# node.net
KiCad netlist of a schematic drawn in EAGLE
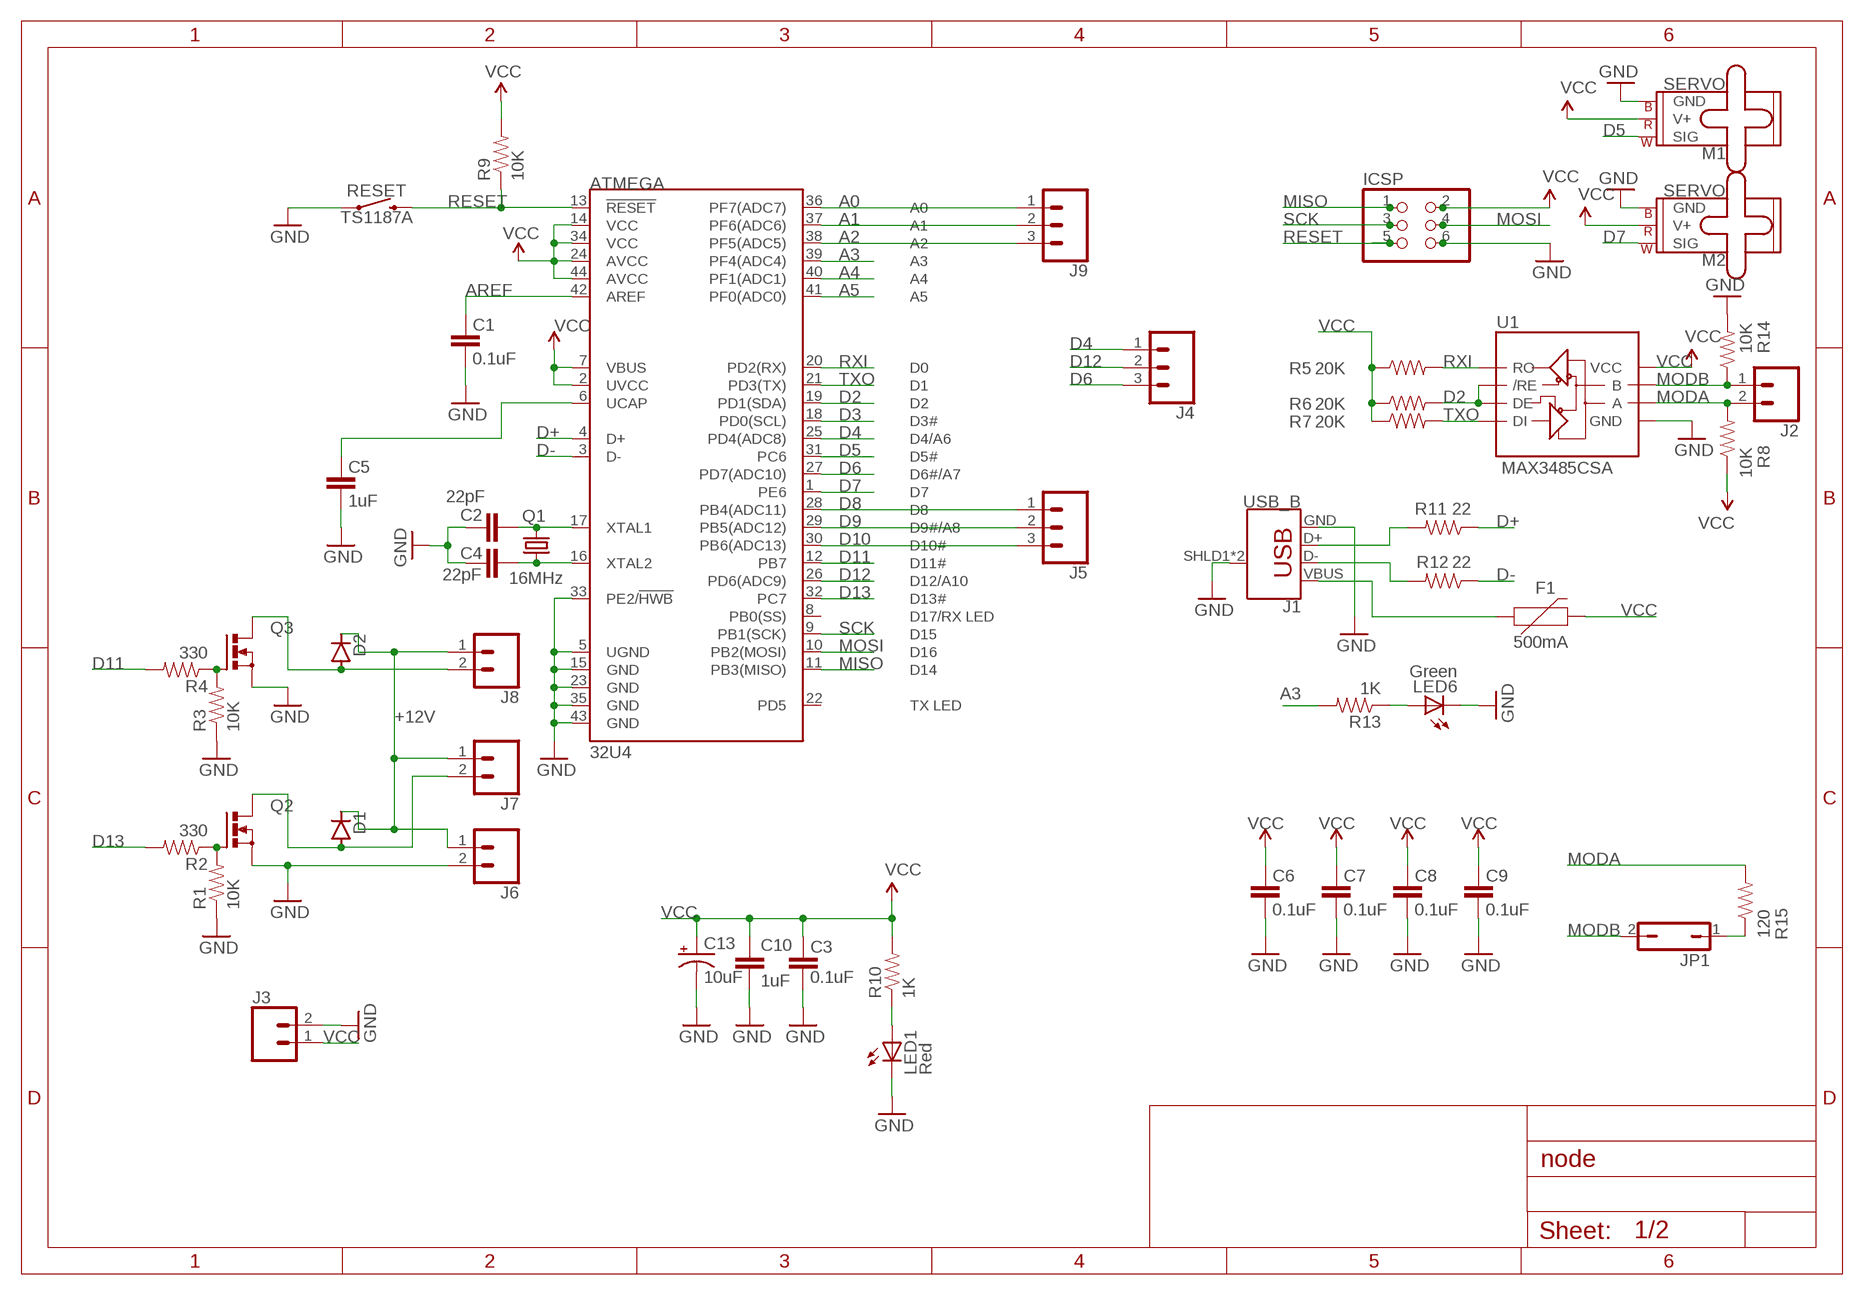
[diagram p0: schematic, sheet 1]
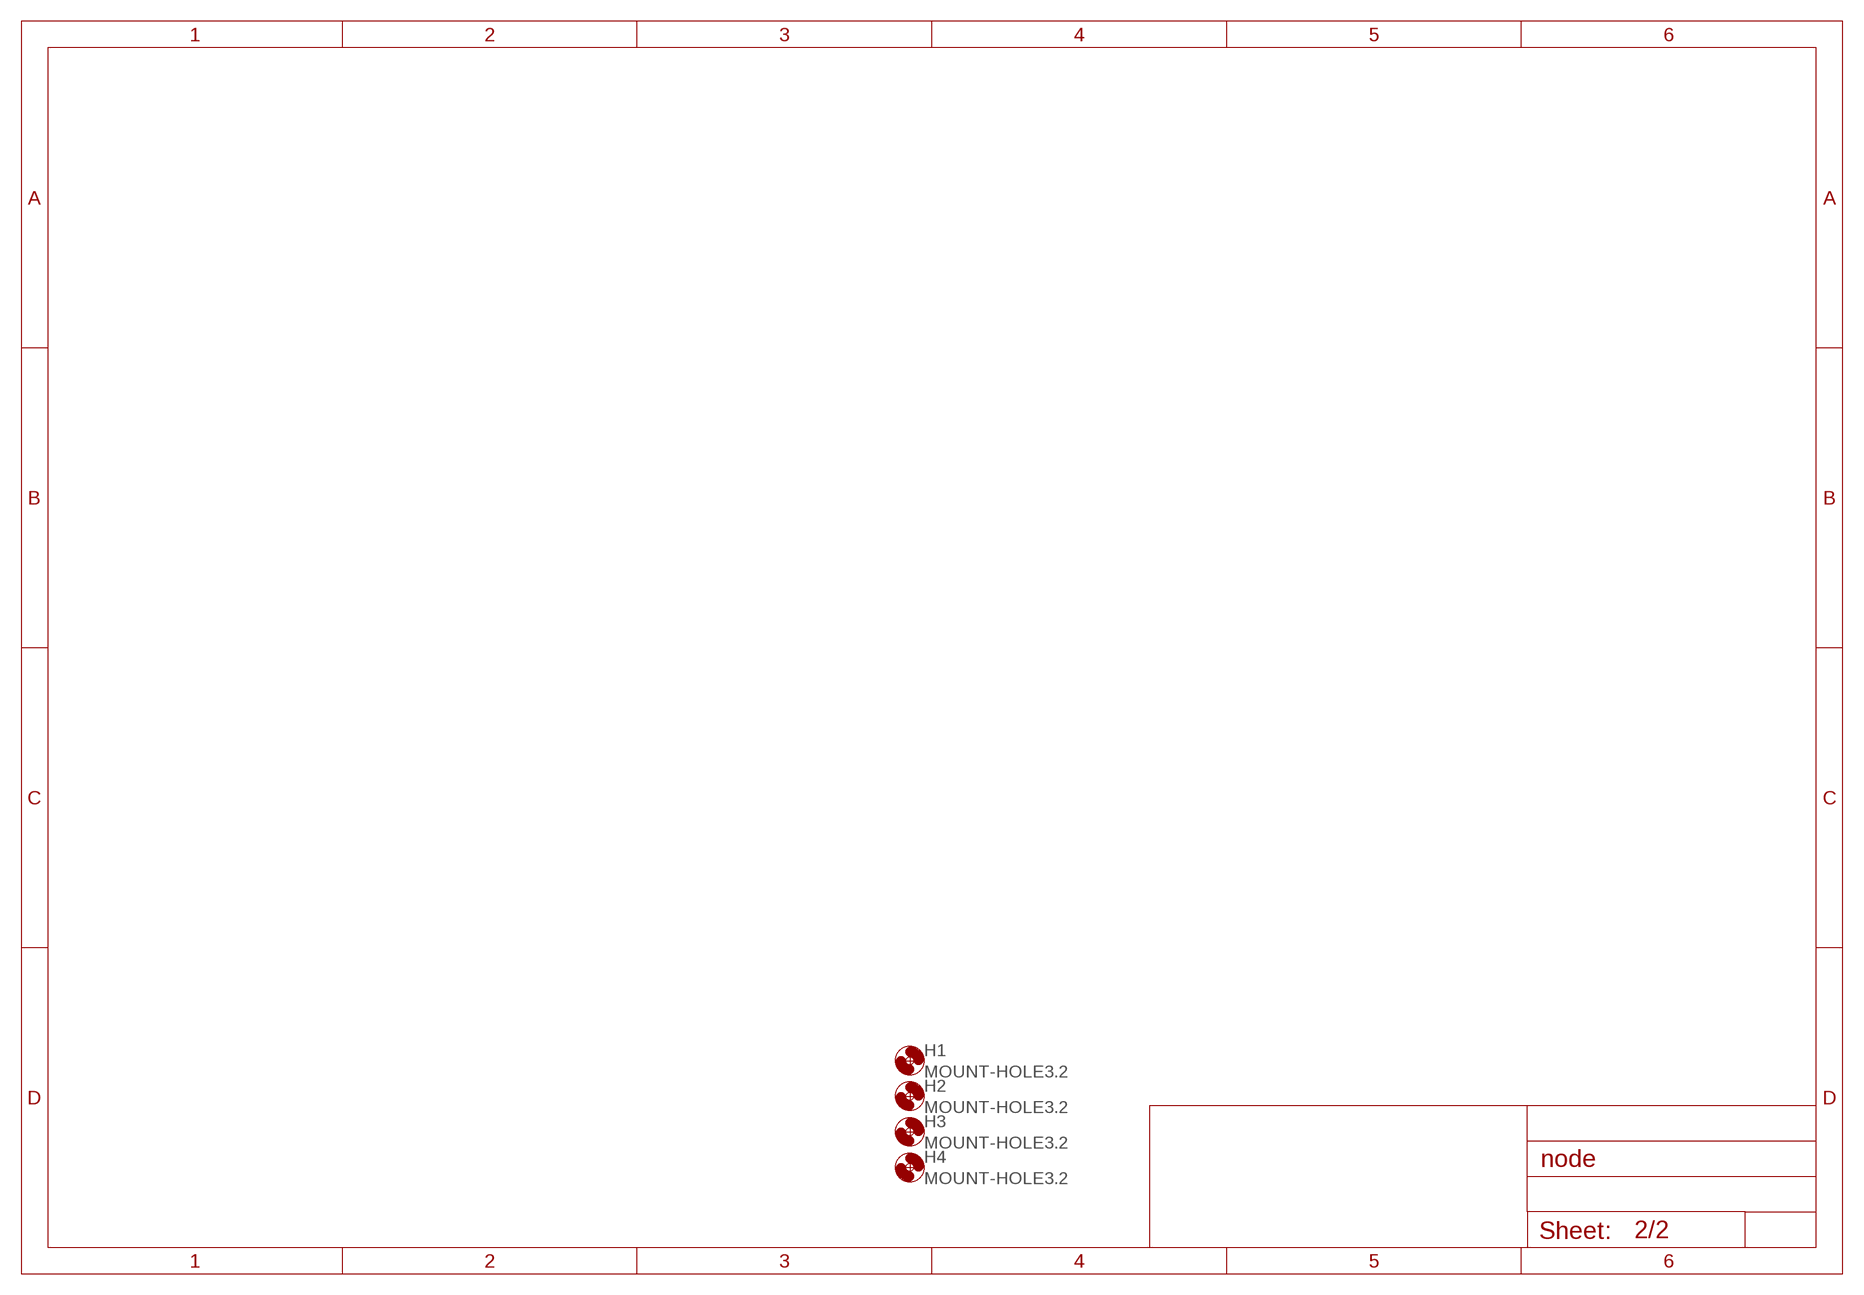
[diagram p1: schematic, sheet 2]

(export (version "E")
  (design (tool "Eeschema 10.0.6"))
  (components
    (comp (ref "H1")
      (value "MOUNT-HOLE3.2")
      (footprint "eagle-import:3,2")
      (libsource (lib "eagle-import") (part "MOUNT-HOLE3.2"))
    )
    (comp (ref "H2")
      (value "MOUNT-HOLE3.2")
      (footprint "eagle-import:3,2")
      (libsource (lib "eagle-import") (part "MOUNT-HOLE3.2"))
    )
    (comp (ref "H3")
      (value "MOUNT-HOLE3.2")
      (footprint "eagle-import:3,2")
      (libsource (lib "eagle-import") (part "MOUNT-HOLE3.2"))
    )
    (comp (ref "H4")
      (value "MOUNT-HOLE3.2")
      (footprint "eagle-import:3,2")
      (libsource (lib "eagle-import") (part "MOUNT-HOLE3.2"))
    )
    (comp (ref "ATMEGA")
      (value "32U4")
      (footprint "eagle-import:QFN-44-NOPAD_1_1")
      (libsource (lib "eagle-import") (part "ATMEGA32U41{colon}1"))
    )
    (comp (ref "C1")
      (value "0.1uF")
      (footprint "eagle-import:0603-CAP")
      (libsource (lib "eagle-import") (part "CAP0603-CAP"))
    )
    (comp (ref "C2")
      (value "22pF")
      (footprint "eagle-import:0603-CAP")
      (libsource (lib "eagle-import") (part "CAP0603-CAP"))
    )
    (comp (ref "C3")
      (value "0.1uF")
      (footprint "eagle-import:0603-CAP")
      (libsource (lib "eagle-import") (part "CAP0603-CAP"))
    )
    (comp (ref "C4")
      (value "22pF")
      (footprint "eagle-import:0603-CAP")
      (libsource (lib "eagle-import") (part "CAP0603-CAP"))
    )
    (comp (ref "C5")
      (value "1uF")
      (footprint "eagle-import:0603-CAP")
      (libsource (lib "eagle-import") (part "CAP0603-CAP"))
    )
    (comp (ref "C6")
      (value "0.1uF")
      (footprint "eagle-import:0603-CAP")
      (libsource (lib "eagle-import") (part "CAP0603-CAP"))
    )
    (comp (ref "C7")
      (value "0.1uF")
      (footprint "eagle-import:0603-CAP")
      (libsource (lib "eagle-import") (part "CAP0603-CAP"))
    )
    (comp (ref "C8")
      (value "0.1uF")
      (footprint "eagle-import:0603-CAP")
      (libsource (lib "eagle-import") (part "CAP0603-CAP"))
    )
    (comp (ref "C9")
      (value "0.1uF")
      (footprint "eagle-import:0603-CAP")
      (libsource (lib "eagle-import") (part "CAP0603-CAP"))
    )
    (comp (ref "C10")
      (value "1uF")
      (footprint "eagle-import:0603-CAP")
      (libsource (lib "eagle-import") (part "CAP0603-CAP"))
    )
    (comp (ref "C13")
      (value "10uF")
      (footprint "eagle-import:EIA3216")
      (libsource (lib "eagle-import") (part "CAP_POL1206"))
    )
    (comp (ref "D1")
      (value "BYS10")
      (footprint "eagle-import:SOD106A")
      (fields (field (name "MPN") "BYS10/45"))
      (libsource (lib "eagle-import") (part "BYS10"))
    )
    (comp (ref "D2")
      (value "BYS10")
      (footprint "eagle-import:SOD106A")
      (fields (field (name "MPN") "BYS10/45"))
      (libsource (lib "eagle-import") (part "BYS10"))
    )
    (comp (ref "F1")
      (value "500mA")
      (footprint "eagle-import:1206")
      (libsource (lib "eagle-import") (part "PPTC_HALF-AMP"))
    )
    (comp (ref "ICSP")
      (value "PINHD-2X3")
      (footprint "eagle-import:2X03")
      (libsource (lib "eagle-import") (part "PINHD-2X3"))
    )
    (comp (ref "J1")
      (value "USB_B")
      (footprint "eagle-import:USB-B-PTH")
      (libsource (lib "eagle-import") (part "USB_B_PTH"))
    )
    (comp (ref "J2")
      (value "CONN_025MM")
      (footprint "eagle-import:SCREWTERMINAL-5MM-2")
      (libsource (lib "eagle-import") (part "CONN_025MM"))
    )
    (comp (ref "J3")
      (value "CONN_025MM")
      (footprint "eagle-import:SCREWTERMINAL-5MM-2")
      (libsource (lib "eagle-import") (part "CONN_025MM"))
    )
    (comp (ref "J4")
      (value "CONN_03-SCREW-5MM")
      (footprint "eagle-import:SCREWTERMINAL-5MM-3")
      (libsource (lib "eagle-import") (part "CONN_03-SCREW-5MM"))
    )
    (comp (ref "J5")
      (value "CONN_03-SCREW-5MM")
      (footprint "eagle-import:SCREWTERMINAL-5MM-3")
      (libsource (lib "eagle-import") (part "CONN_03-SCREW-5MM"))
    )
    (comp (ref "J6")
      (value "CONN_025MM")
      (footprint "eagle-import:SCREWTERMINAL-5MM-2")
      (libsource (lib "eagle-import") (part "CONN_025MM"))
    )
    (comp (ref "J7")
      (value "CONN_025MM")
      (footprint "eagle-import:SCREWTERMINAL-5MM-2")
      (libsource (lib "eagle-import") (part "CONN_025MM"))
    )
    (comp (ref "J8")
      (value "CONN_025MM")
      (footprint "eagle-import:SCREWTERMINAL-5MM-2")
      (libsource (lib "eagle-import") (part "CONN_025MM"))
    )
    (comp (ref "J9")
      (value "CONN_03-SCREW-5MM")
      (footprint "eagle-import:SCREWTERMINAL-5MM-3")
      (libsource (lib "eagle-import") (part "CONN_03-SCREW-5MM"))
    )
    (comp (ref "JP1")
      (value "JP1Q")
      (footprint "eagle-import:JP1")
      (libsource (lib "eagle-import") (part "JP1Q"))
    )
    (comp (ref "LED1")
      (value "Red")
      (footprint "eagle-import:LED-0603")
      (libsource (lib "eagle-import") (part "LED0603"))
    )
    (comp (ref "LED6")
      (value "Green")
      (footprint "eagle-import:LED-0603")
      (libsource (lib "eagle-import") (part "LED0603"))
    )
    (comp (ref "M1")
      (value "SERVO")
      (footprint "eagle-import:1X03")
      (libsource (lib "eagle-import") (part "SERVO"))
    )
    (comp (ref "M2")
      (value "SERVO")
      (footprint "eagle-import:1X03")
      (libsource (lib "eagle-import") (part "SERVO"))
    )
    (comp (ref "Q1")
      (value "16MHz")
      (footprint "eagle-import:3.2X2.5_KX-7")
      (libsource (lib "eagle-import") (part "KX-7"))
    )
    (comp (ref "Q2")
      (value "PMOSFET_NTO220BV")
      (footprint "eagle-import:TO220BV")
      (libsource (lib "eagle-import") (part "PMOSFET_NTO220BV"))
    )
    (comp (ref "Q3")
      (value "PMOSFET_NTO220BV")
      (footprint "eagle-import:TO220BV")
      (libsource (lib "eagle-import") (part "PMOSFET_NTO220BV"))
    )
    (comp (ref "R1")
      (value "10K")
      (footprint "eagle-import:0603-RES")
      (libsource (lib "eagle-import") (part "RESISTOR0603-RES"))
    )
    (comp (ref "R2")
      (value "330")
      (footprint "eagle-import:0603-RES")
      (libsource (lib "eagle-import") (part "RESISTOR0603-RES"))
    )
    (comp (ref "R3")
      (value "10K")
      (footprint "eagle-import:0603-RES")
      (libsource (lib "eagle-import") (part "RESISTOR0603-RES"))
    )
    (comp (ref "R4")
      (value "330")
      (footprint "eagle-import:0603-RES")
      (libsource (lib "eagle-import") (part "RESISTOR0603-RES"))
    )
    (comp (ref "R5")
      (value "20K")
      (footprint "eagle-import:0603-RES")
      (libsource (lib "eagle-import") (part "RESISTOR0603-RES"))
    )
    (comp (ref "R6")
      (value "20K")
      (footprint "eagle-import:0603-RES")
      (libsource (lib "eagle-import") (part "RESISTOR0603-RES"))
    )
    (comp (ref "R7")
      (value "20K")
      (footprint "eagle-import:0603-RES")
      (libsource (lib "eagle-import") (part "RESISTOR0603-RES"))
    )
    (comp (ref "R8")
      (value "10K")
      (footprint "eagle-import:0603-RES")
      (libsource (lib "eagle-import") (part "RESISTOR0603-RES"))
    )
    (comp (ref "R9")
      (value "10K")
      (footprint "eagle-import:0603-RES")
      (libsource (lib "eagle-import") (part "RESISTOR0603-RES"))
    )
    (comp (ref "R10")
      (value "1K")
      (footprint "eagle-import:0603-RES")
      (libsource (lib "eagle-import") (part "RESISTOR0603-RES"))
    )
    (comp (ref "R11")
      (value "22")
      (footprint "eagle-import:0603-RES")
      (libsource (lib "eagle-import") (part "RESISTOR0603-RES"))
    )
    (comp (ref "R12")
      (value "22")
      (footprint "eagle-import:0603-RES")
      (libsource (lib "eagle-import") (part "RESISTOR0603-RES"))
    )
    (comp (ref "R13")
      (value "1K")
      (footprint "eagle-import:0603-RES")
      (libsource (lib "eagle-import") (part "RESISTOR0603-RES"))
    )
    (comp (ref "R14")
      (value "10K")
      (footprint "eagle-import:0603-RES")
      (libsource (lib "eagle-import") (part "RESISTOR0603-RES"))
    )
    (comp (ref "R15")
      (value "120")
      (footprint "eagle-import:0603-RES")
      (libsource (lib "eagle-import") (part "RESISTOR0603-RES"))
    )
    (comp (ref "RESET")
      (value "TS1187A")
      (footprint "eagle-import:TACTILE_SWITCH_SMD_5.2MM")
      (libsource (lib "eagle-import") (part "MOMENTARY-SWITCH-SPST-SMD-5.2MM"))
    )
    (comp (ref "U1")
      (value "MAX3485CSA")
      (footprint "eagle-import:SO08")
      (libsource (lib "eagle-import") (part "RS485SOIC"))
    )
  )
  (nets
    (net (code "1") (name "+12V") (class "Default")
      (node (ref "D1") (pin "K") (pinfunction "K_K") (pintype "passive"))
      (node (ref "D2") (pin "K") (pinfunction "K_K") (pintype "passive"))
      (node (ref "J6") (pin "1") (pinfunction "1_1") (pintype "passive"))
      (node (ref "J7") (pin "1") (pinfunction "1_1") (pintype "passive"))
      (node (ref "J8") (pin "1") (pinfunction "1_1") (pintype "passive"))
    )
    (net (code "2") (name "A0") (class "Default")
      (node (ref "ATMEGA") (pin "36") (pinfunction "PF7(ADC7)_36") (pintype "bidirectional"))
      (node (ref "J9") (pin "1") (pinfunction "1_1") (pintype "passive"))
    )
    (net (code "3") (name "A1") (class "Default")
      (node (ref "ATMEGA") (pin "37") (pinfunction "PF6(ADC6)_37") (pintype "bidirectional"))
      (node (ref "J9") (pin "2") (pinfunction "2_2") (pintype "passive"))
    )
    (net (code "4") (name "A2") (class "Default")
      (node (ref "ATMEGA") (pin "38") (pinfunction "PF5(ADC5)_38") (pintype "bidirectional"))
      (node (ref "J9") (pin "3") (pinfunction "3_3") (pintype "passive"))
    )
    (net (code "5") (name "A3") (class "Default")
      (node (ref "ATMEGA") (pin "39") (pinfunction "PF4(ADC4)_39") (pintype "bidirectional"))
      (node (ref "R13") (pin "2") (pinfunction "2_2") (pintype "passive"))
    )
    (net (code "6") (name "A4") (class "Default")
      (node (ref "ATMEGA") (pin "40") (pinfunction "PF1(ADC1)_40") (pintype "bidirectional"))
    )
    (net (code "7") (name "A5") (class "Default")
      (node (ref "ATMEGA") (pin "41") (pinfunction "PF0(ADC0)_41") (pintype "bidirectional"))
    )
    (net (code "8") (name "AREF") (class "Default")
      (node (ref "ATMEGA") (pin "42") (pinfunction "AREF_42") (pintype "bidirectional"))
      (node (ref "C1") (pin "2") (pinfunction "2_2") (pintype "passive"))
    )
    (net (code "9") (name "D+") (class "Default")
      (node (ref "ATMEGA") (pin "4") (pinfunction "D+_4") (pintype "bidirectional"))
      (node (ref "R11") (pin "1") (pinfunction "1_1") (pintype "passive"))
    )
    (net (code "10") (name "D-") (class "Default")
      (node (ref "ATMEGA") (pin "3") (pinfunction "D-_3") (pintype "bidirectional"))
      (node (ref "R12") (pin "1") (pinfunction "1_1") (pintype "passive"))
    )
    (net (code "11") (name "D2") (class "Default")
      (node (ref "ATMEGA") (pin "19") (pinfunction "PD1(SDA)_19") (pintype "bidirectional"))
      (node (ref "R6") (pin "2") (pinfunction "2_2") (pintype "passive"))
      (node (ref "U1") (pin "2") (pinfunction "/RE_2") (pintype "bidirectional"))
      (node (ref "U1") (pin "3") (pinfunction "DE_3") (pintype "bidirectional"))
    )
    (net (code "12") (name "D3") (class "Default")
      (node (ref "ATMEGA") (pin "18") (pinfunction "PD0(SCL)_18") (pintype "bidirectional"))
    )
    (net (code "13") (name "D4") (class "Default")
      (node (ref "ATMEGA") (pin "25") (pinfunction "PD4(ADC8)_25") (pintype "bidirectional"))
      (node (ref "J4") (pin "1") (pinfunction "1_1") (pintype "passive"))
    )
    (net (code "14") (name "D5") (class "Default")
      (node (ref "ATMEGA") (pin "31") (pinfunction "PC6_31") (pintype "bidirectional"))
      (node (ref "M1") (pin "1") (pinfunction "SIG_1") (pintype "bidirectional"))
    )
    (net (code "15") (name "D6") (class "Default")
      (node (ref "ATMEGA") (pin "27") (pinfunction "PD7(ADC10)_27") (pintype "bidirectional"))
      (node (ref "J4") (pin "3") (pinfunction "3_3") (pintype "passive"))
    )
    (net (code "16") (name "D7") (class "Default")
      (node (ref "ATMEGA") (pin "1") (pinfunction "PE6_1") (pintype "bidirectional"))
      (node (ref "M2") (pin "1") (pinfunction "SIG_1") (pintype "bidirectional"))
    )
    (net (code "17") (name "D8") (class "Default")
      (node (ref "ATMEGA") (pin "28") (pinfunction "PB4(ADC11)_28") (pintype "bidirectional"))
      (node (ref "J5") (pin "1") (pinfunction "1_1") (pintype "passive"))
    )
    (net (code "18") (name "D9") (class "Default")
      (node (ref "ATMEGA") (pin "29") (pinfunction "PB5(ADC12)_29") (pintype "bidirectional"))
      (node (ref "J5") (pin "2") (pinfunction "2_2") (pintype "passive"))
    )
    (net (code "19") (name "D10") (class "Default")
      (node (ref "ATMEGA") (pin "30") (pinfunction "PB6(ADC13)_30") (pintype "bidirectional"))
      (node (ref "J5") (pin "3") (pinfunction "3_3") (pintype "passive"))
    )
    (net (code "20") (name "D11") (class "Default")
      (node (ref "ATMEGA") (pin "12") (pinfunction "PB7_12") (pintype "bidirectional"))
      (node (ref "R4") (pin "2") (pinfunction "2_2") (pintype "passive"))
    )
    (net (code "21") (name "D12") (class "Default")
      (node (ref "ATMEGA") (pin "26") (pinfunction "PD6(ADC9)_26") (pintype "bidirectional"))
      (node (ref "J4") (pin "2") (pinfunction "2_2") (pintype "passive"))
    )
    (net (code "22") (name "D13") (class "Default")
      (node (ref "ATMEGA") (pin "32") (pinfunction "PC7_32") (pintype "bidirectional"))
      (node (ref "R2") (pin "2") (pinfunction "2_2") (pintype "passive"))
    )
    (net (code "23") (name "GND") (class "Default")
      (node (ref "ATMEGA") (pin "15") (pinfunction "GND_15") (pintype "bidirectional"))
      (node (ref "ATMEGA") (pin "23") (pinfunction "GND_23") (pintype "bidirectional"))
      (node (ref "ATMEGA") (pin "33") (pinfunction "PE2/~{HWB}_33") (pintype "bidirectional"))
      (node (ref "ATMEGA") (pin "35") (pinfunction "GND_35") (pintype "bidirectional"))
      (node (ref "ATMEGA") (pin "43") (pinfunction "GND_43") (pintype "bidirectional"))
      (node (ref "ATMEGA") (pin "5") (pinfunction "UGND_5") (pintype "bidirectional"))
      (node (ref "C1") (pin "1") (pinfunction "1_1") (pintype "passive"))
      (node (ref "C10") (pin "2") (pinfunction "2_2") (pintype "passive"))
      (node (ref "C13") (pin "C") (pinfunction "-_C") (pintype "passive"))
      (node (ref "C2") (pin "2") (pinfunction "2_2") (pintype "passive"))
      (node (ref "C3") (pin "1") (pinfunction "1_1") (pintype "passive"))
      (node (ref "C4") (pin "2") (pinfunction "2_2") (pintype "passive"))
      (node (ref "C5") (pin "1") (pinfunction "1_1") (pintype "passive"))
      (node (ref "C6") (pin "1") (pinfunction "1_1") (pintype "passive"))
      (node (ref "C7") (pin "1") (pinfunction "1_1") (pintype "passive"))
      (node (ref "C8") (pin "1") (pinfunction "1_1") (pintype "passive"))
      (node (ref "C9") (pin "1") (pinfunction "1_1") (pintype "passive"))
      (node (ref "ICSP") (pin "6") (pinfunction "6_6") (pintype "passive"))
      (node (ref "J1") (pin "GND") (pinfunction "GND_GND") (pintype "power_in"))
      (node (ref "J1") (pin "SHLD1") (pinfunction "SHIELD_SHLD1") (pintype "bidirectional"))
      (node (ref "J1") (pin "SHLD2") (pinfunction "SHIELD_SHLD2") (pintype "bidirectional"))
      (node (ref "J3") (pin "2") (pinfunction "2_2") (pintype "passive"))
      (node (ref "J6") (pin "2") (pinfunction "2_2") (pintype "passive"))
      (node (ref "LED1") (pin "C") (pinfunction "C_C") (pintype "passive"))
      (node (ref "LED6") (pin "C") (pinfunction "C_C") (pintype "passive"))
      (node (ref "M1") (pin "3") (pinfunction "GND_3") (pintype "bidirectional"))
      (node (ref "M2") (pin "3") (pinfunction "GND_3") (pintype "bidirectional"))
      (node (ref "Q2") (pin "S") (pinfunction "S_S") (pintype "passive"))
      (node (ref "Q3") (pin "S") (pinfunction "S_S") (pintype "passive"))
      (node (ref "R1") (pin "1") (pinfunction "1_1") (pintype "passive"))
      (node (ref "R14") (pin "2") (pinfunction "2_2") (pintype "passive"))
      (node (ref "R3") (pin "1") (pinfunction "1_1") (pintype "passive"))
      (node (ref "RESET") (pin "1") (pinfunction "1_1") (pintype "passive"))
      (node (ref "U1") (pin "5") (pinfunction "GND_5") (pintype "bidirectional"))
    )
    (net (code "24") (name "MISO") (class "Default")
      (node (ref "ATMEGA") (pin "11") (pinfunction "PB3(MISO)_11") (pintype "bidirectional"))
      (node (ref "ICSP") (pin "1") (pinfunction "1_1") (pintype "passive"))
    )
    (net (code "25") (name "MODA") (class "Default")
      (node (ref "J2") (pin "2") (pinfunction "2_2") (pintype "passive"))
      (node (ref "R15") (pin "2") (pinfunction "2_2") (pintype "passive"))
      (node (ref "R8") (pin "2") (pinfunction "2_2") (pintype "passive"))
      (node (ref "U1") (pin "6") (pinfunction "A_6") (pintype "bidirectional"))
    )
    (net (code "26") (name "MODB") (class "Default")
      (node (ref "J2") (pin "1") (pinfunction "1_1") (pintype "passive"))
      (node (ref "JP1") (pin "2") (pinfunction "2_2") (pintype "passive"))
      (node (ref "R14") (pin "1") (pinfunction "1_1") (pintype "passive"))
      (node (ref "U1") (pin "7") (pinfunction "B_7") (pintype "bidirectional"))
    )
    (net (code "27") (name "MOSI") (class "Default")
      (node (ref "ATMEGA") (pin "10") (pinfunction "PB2(MOSI)_10") (pintype "bidirectional"))
      (node (ref "ICSP") (pin "4") (pinfunction "4_4") (pintype "passive"))
    )
    (net (code "28") (name "Net-(ATMEGA-UCAP)") (class "Default")
      (node (ref "ATMEGA") (pin "6") (pinfunction "UCAP_6") (pintype "bidirectional"))
      (node (ref "C5") (pin "2") (pinfunction "2_2") (pintype "passive"))
    )
    (net (code "29") (name "Net-(ATMEGA-XTAL1)") (class "Default")
      (node (ref "ATMEGA") (pin "17") (pinfunction "XTAL1_17") (pintype "bidirectional"))
      (node (ref "C2") (pin "1") (pinfunction "1_1") (pintype "passive"))
      (node (ref "Q1") (pin "3") (pinfunction "2_3") (pintype "passive"))
    )
    (net (code "30") (name "Net-(ATMEGA-XTAL2)") (class "Default")
      (node (ref "ATMEGA") (pin "16") (pinfunction "XTAL2_16") (pintype "bidirectional"))
      (node (ref "C4") (pin "1") (pinfunction "1_1") (pintype "passive"))
      (node (ref "Q1") (pin "1") (pinfunction "1_1") (pintype "passive"))
    )
    (net (code "31") (name "Net-(D1-PadA)") (class "Default")
      (node (ref "D1") (pin "A") (pinfunction "A_A") (pintype "passive"))
      (node (ref "J7") (pin "2") (pinfunction "2_2") (pintype "passive"))
      (node (ref "Q2") (pin "D") (pinfunction "D_D") (pintype "passive"))
    )
    (net (code "32") (name "Net-(D2-PadA)") (class "Default")
      (node (ref "D2") (pin "A") (pinfunction "A_A") (pintype "passive"))
      (node (ref "J8") (pin "2") (pinfunction "2_2") (pintype "passive"))
      (node (ref "Q3") (pin "D") (pinfunction "D_D") (pintype "passive"))
    )
    (net (code "33") (name "Net-(F1-Pad1)") (class "Default")
      (node (ref "F1") (pin "1") (pinfunction "1_1") (pintype "bidirectional"))
      (node (ref "J1") (pin "VBUS") (pinfunction "VBUS_VBUS") (pintype "power_in"))
    )
    (net (code "34") (name "Net-(J1-PadD+)") (class "Default")
      (node (ref "J1") (pin "D+") (pinfunction "D+_D+") (pintype "bidirectional"))
      (node (ref "R11") (pin "2") (pinfunction "2_2") (pintype "passive"))
    )
    (net (code "35") (name "Net-(J1-PadD-)") (class "Default")
      (node (ref "J1") (pin "D-") (pinfunction "D-_D-") (pintype "bidirectional"))
      (node (ref "R12") (pin "2") (pinfunction "2_2") (pintype "passive"))
    )
    (net (code "36") (name "Net-(JP1-Pad1)") (class "Default")
      (node (ref "JP1") (pin "1") (pinfunction "1_1") (pintype "passive"))
      (node (ref "R15") (pin "1") (pinfunction "1_1") (pintype "passive"))
    )
    (net (code "37") (name "Net-(LED1-PadA)") (class "Default")
      (node (ref "LED1") (pin "A") (pinfunction "A_A") (pintype "passive"))
      (node (ref "R10") (pin "1") (pinfunction "1_1") (pintype "passive"))
    )
    (net (code "38") (name "Net-(LED6-PadA)") (class "Default")
      (node (ref "LED6") (pin "A") (pinfunction "A_A") (pintype "passive"))
      (node (ref "R13") (pin "1") (pinfunction "1_1") (pintype "passive"))
    )
    (net (code "39") (name "Net-(Q2-PadG)") (class "Default")
      (node (ref "Q2") (pin "G") (pinfunction "G_G") (pintype "passive"))
      (node (ref "R1") (pin "2") (pinfunction "2_2") (pintype "passive"))
      (node (ref "R2") (pin "1") (pinfunction "1_1") (pintype "passive"))
    )
    (net (code "40") (name "Net-(Q3-PadG)") (class "Default")
      (node (ref "Q3") (pin "G") (pinfunction "G_G") (pintype "passive"))
      (node (ref "R3") (pin "2") (pinfunction "2_2") (pintype "passive"))
      (node (ref "R4") (pin "1") (pinfunction "1_1") (pintype "passive"))
    )
    (net (code "41") (name "RESET") (class "Default")
      (node (ref "ATMEGA") (pin "13") (pinfunction "~{RESET}_13") (pintype "bidirectional"))
      (node (ref "ICSP") (pin "5") (pinfunction "5_5") (pintype "passive"))
      (node (ref "R9") (pin "1") (pinfunction "1_1") (pintype "passive"))
      (node (ref "RESET") (pin "3") (pinfunction "2_3") (pintype "passive"))
    )
    (net (code "42") (name "RXI") (class "Default")
      (node (ref "ATMEGA") (pin "20") (pinfunction "PD2(RX)_20") (pintype "bidirectional"))
      (node (ref "R5") (pin "2") (pinfunction "2_2") (pintype "passive"))
      (node (ref "U1") (pin "1") (pinfunction "RO_1") (pintype "bidirectional"))
    )
    (net (code "43") (name "SCK") (class "Default")
      (node (ref "ATMEGA") (pin "9") (pinfunction "PB1(SCK)_9") (pintype "bidirectional"))
      (node (ref "ICSP") (pin "3") (pinfunction "3_3") (pintype "passive"))
    )
    (net (code "44") (name "TXO") (class "Default")
      (node (ref "ATMEGA") (pin "21") (pinfunction "PD3(TX)_21") (pintype "bidirectional"))
      (node (ref "R7") (pin "2") (pinfunction "2_2") (pintype "passive"))
      (node (ref "U1") (pin "4") (pinfunction "DI_4") (pintype "bidirectional"))
    )
    (net (code "45") (name "VCC") (class "Default")
      (node (ref "ATMEGA") (pin "14") (pinfunction "VCC_14") (pintype "bidirectional"))
      (node (ref "ATMEGA") (pin "2") (pinfunction "UVCC_2") (pintype "bidirectional"))
      (node (ref "ATMEGA") (pin "24") (pinfunction "AVCC_24") (pintype "bidirectional"))
      (node (ref "ATMEGA") (pin "34") (pinfunction "VCC_34") (pintype "bidirectional"))
      (node (ref "ATMEGA") (pin "44") (pinfunction "AVCC_44") (pintype "bidirectional"))
      (node (ref "ATMEGA") (pin "7") (pinfunction "VBUS_7") (pintype "bidirectional"))
      (node (ref "C10") (pin "1") (pinfunction "1_1") (pintype "passive"))
      (node (ref "C13") (pin "A") (pinfunction "+_A") (pintype "passive"))
      (node (ref "C3") (pin "2") (pinfunction "2_2") (pintype "passive"))
      (node (ref "C6") (pin "2") (pinfunction "2_2") (pintype "passive"))
      (node (ref "C7") (pin "2") (pinfunction "2_2") (pintype "passive"))
      (node (ref "C8") (pin "2") (pinfunction "2_2") (pintype "passive"))
      (node (ref "C9") (pin "2") (pinfunction "2_2") (pintype "passive"))
      (node (ref "F1") (pin "2") (pinfunction "2_2") (pintype "bidirectional"))
      (node (ref "ICSP") (pin "2") (pinfunction "2_2") (pintype "passive"))
      (node (ref "J3") (pin "1") (pinfunction "1_1") (pintype "passive"))
      (node (ref "M1") (pin "2") (pinfunction "V+_2") (pintype "bidirectional"))
      (node (ref "M2") (pin "2") (pinfunction "V+_2") (pintype "bidirectional"))
      (node (ref "R10") (pin "2") (pinfunction "2_2") (pintype "passive"))
      (node (ref "R5") (pin "1") (pinfunction "1_1") (pintype "passive"))
      (node (ref "R6") (pin "1") (pinfunction "1_1") (pintype "passive"))
      (node (ref "R7") (pin "1") (pinfunction "1_1") (pintype "passive"))
      (node (ref "R8") (pin "1") (pinfunction "1_1") (pintype "passive"))
      (node (ref "R9") (pin "2") (pinfunction "2_2") (pintype "passive"))
      (node (ref "U1") (pin "8") (pinfunction "VCC_8") (pintype "bidirectional"))
    )
    (net (code "46") (name "unconnected-(ATMEGA-PB0(SS)-Pad8)") (class "Default")
      (node (ref "ATMEGA") (pin "8") (pinfunction "PB0(SS)_8") (pintype "bidirectional"))
    )
    (net (code "47") (name "unconnected-(ATMEGA-PD5-Pad22)") (class "Default")
      (node (ref "ATMEGA") (pin "22") (pinfunction "PD5_22") (pintype "bidirectional"))
    )
  )
)
